# nightlight.net
KiCad netlist of a schematic drawn in EAGLE
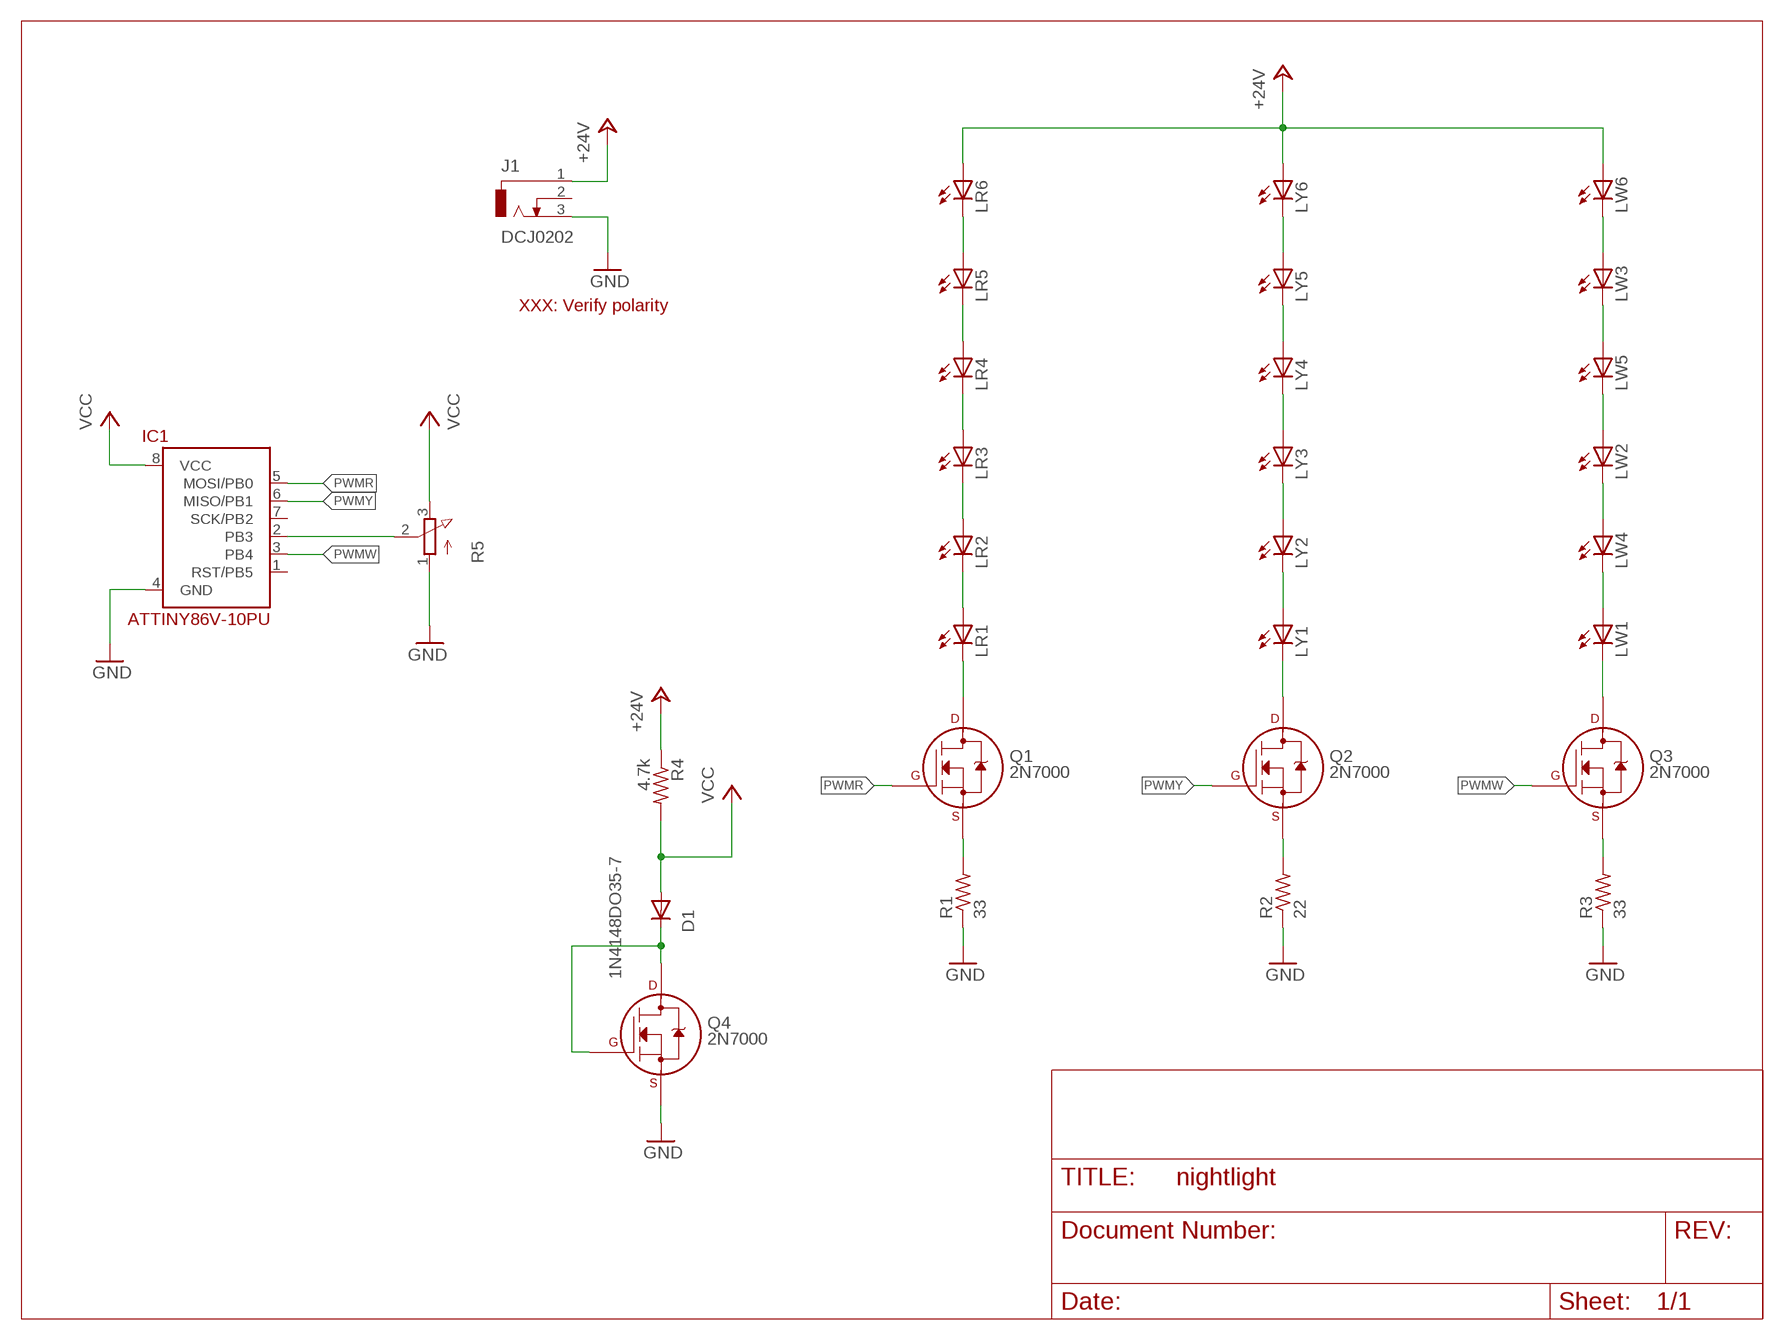
[diagram p0: schematic, sheet 1]

(export (version "E")
  (design (tool "Eeschema 10.0.6"))
  (components
    (comp (ref "D1")
      (value "1N4148DO35-7")
      (footprint "eagle-import:DO35-7")
      (libsource (lib "eagle-import") (part "1N4148DO35-7"))
    )
    (comp (ref "IC1")
      (value "ATTINY86V-10PU")
      (footprint "eagle-import:DIL08")
      (libsource (lib "eagle-import") (part "ATTINY13V-10PU"))
    )
    (comp (ref "J1")
      (value "DCJ0202")
      (footprint "eagle-import:DCJ0202")
      (libsource (lib "eagle-import") (part "DCJ0202"))
    )
    (comp (ref "LR1")
      (value "LED5MM")
      (footprint "eagle-import:LED5MM")
      (libsource (lib "eagle-import") (part "led_LED5MM"))
    )
    (comp (ref "LR2")
      (value "LED5MM")
      (footprint "eagle-import:LED5MM")
      (libsource (lib "eagle-import") (part "led_LED5MM"))
    )
    (comp (ref "LR3")
      (value "LED5MM")
      (footprint "eagle-import:LED5MM")
      (libsource (lib "eagle-import") (part "led_LED5MM"))
    )
    (comp (ref "LR4")
      (value "LED5MM")
      (footprint "eagle-import:LED5MM")
      (libsource (lib "eagle-import") (part "led_LED5MM"))
    )
    (comp (ref "LR5")
      (value "LED5MM")
      (footprint "eagle-import:LED5MM")
      (libsource (lib "eagle-import") (part "led_LED5MM"))
    )
    (comp (ref "LR6")
      (value "LED5MM")
      (footprint "eagle-import:LED5MM")
      (libsource (lib "eagle-import") (part "led_LED5MM"))
    )
    (comp (ref "LW1")
      (value "LED5MM")
      (footprint "eagle-import:LED5MM")
      (libsource (lib "eagle-import") (part "led_LED5MM"))
    )
    (comp (ref "LW2")
      (value "LED5MM")
      (footprint "eagle-import:LED5MM")
      (libsource (lib "eagle-import") (part "led_LED5MM"))
    )
    (comp (ref "LW3")
      (value "LED5MM")
      (footprint "eagle-import:LED5MM")
      (libsource (lib "eagle-import") (part "led_LED5MM"))
    )
    (comp (ref "LW4")
      (value "LED3MM")
      (footprint "eagle-import:LED3MM")
      (libsource (lib "eagle-import") (part "LED3MM"))
    )
    (comp (ref "LW5")
      (value "LED3MM")
      (footprint "eagle-import:LED3MM")
      (libsource (lib "eagle-import") (part "LED3MM"))
    )
    (comp (ref "LW6")
      (value "LED3MM")
      (footprint "eagle-import:LED3MM")
      (libsource (lib "eagle-import") (part "LED3MM"))
    )
    (comp (ref "LY1")
      (value "LED5MM")
      (footprint "eagle-import:LED5MM")
      (libsource (lib "eagle-import") (part "led_LED5MM"))
    )
    (comp (ref "LY2")
      (value "LED5MM")
      (footprint "eagle-import:LED5MM")
      (libsource (lib "eagle-import") (part "led_LED5MM"))
    )
    (comp (ref "LY3")
      (value "LED5MM")
      (footprint "eagle-import:LED5MM")
      (libsource (lib "eagle-import") (part "led_LED5MM"))
    )
    (comp (ref "LY4")
      (value "LED5MM")
      (footprint "eagle-import:LED5MM")
      (libsource (lib "eagle-import") (part "led_LED5MM"))
    )
    (comp (ref "LY5")
      (value "LED5MM")
      (footprint "eagle-import:LED5MM")
      (libsource (lib "eagle-import") (part "led_LED5MM"))
    )
    (comp (ref "LY6")
      (value "LED5MM")
      (footprint "eagle-import:LED5MM")
      (libsource (lib "eagle-import") (part "led_LED5MM"))
    )
    (comp (ref "Q1")
      (value "2N7000")
      (footprint "eagle-import:TO-92")
      (libsource (lib "eagle-import") (part "2N700_TO920"))
    )
    (comp (ref "Q2")
      (value "2N7000")
      (footprint "eagle-import:TO-92")
      (libsource (lib "eagle-import") (part "2N700_TO920"))
    )
    (comp (ref "Q3")
      (value "2N7000")
      (footprint "eagle-import:TO-92")
      (libsource (lib "eagle-import") (part "2N700_TO920"))
    )
    (comp (ref "Q4")
      (value "2N7000")
      (footprint "eagle-import:TO-92")
      (libsource (lib "eagle-import") (part "2N700_TO920"))
    )
    (comp (ref "R1")
      (value "33")
      (footprint "eagle-import:0207_10")
      (libsource (lib "eagle-import") (part "R-US_0207/10"))
    )
    (comp (ref "R2")
      (value "22")
      (footprint "eagle-import:0207_10")
      (libsource (lib "eagle-import") (part "R-US_0207/10"))
    )
    (comp (ref "R3")
      (value "33")
      (footprint "eagle-import:0207_10")
      (libsource (lib "eagle-import") (part "R-US_0207/10"))
    )
    (comp (ref "R4")
      (value "4.7k")
      (footprint "eagle-import:0207_10")
      (libsource (lib "eagle-import") (part "R-US_0207/10"))
    )
    (comp (ref "R5")
      (value "3RP/1610N")
      (footprint "eagle-import:3RP_1610N")
      (libsource (lib "eagle-import") (part "3RP/1610N"))
    )
  )
  (nets
    (net (code "1") (name "+24V") (class "Default")
      (node (ref "J1") (pin "1") (pinfunction "1_1") (pintype "passive"))
      (node (ref "LR6") (pin "A") (pinfunction "A_A") (pintype "passive"))
      (node (ref "LW6") (pin "A") (pinfunction "A_A") (pintype "passive"))
      (node (ref "LY6") (pin "A") (pinfunction "A_A") (pintype "passive"))
      (node (ref "R4") (pin "1") (pinfunction "1_1") (pintype "passive"))
    )
    (net (code "2") (name "GND") (class "Default")
      (node (ref "IC1") (pin "4") (pinfunction "GND_4") (pintype "power_in"))
      (node (ref "J1") (pin "3") (pinfunction "3_3") (pintype "passive"))
      (node (ref "Q4") (pin "1") (pinfunction "S_1") (pintype "bidirectional"))
      (node (ref "R1") (pin "1") (pinfunction "1_1") (pintype "passive"))
      (node (ref "R2") (pin "1") (pinfunction "1_1") (pintype "passive"))
      (node (ref "R3") (pin "1") (pinfunction "1_1") (pintype "passive"))
      (node (ref "R5") (pin "1") (pinfunction "A_1") (pintype "passive"))
    )
    (net (code "3") (name "Net-(IC1-PB3)") (class "Default")
      (node (ref "IC1") (pin "2") (pinfunction "PB3_2") (pintype "bidirectional"))
      (node (ref "R5") (pin "2") (pinfunction "S_2") (pintype "passive"))
    )
    (net (code "4") (name "Net-(LR1-C)") (class "Default")
      (node (ref "LR1") (pin "K") (pinfunction "C_K") (pintype "passive"))
      (node (ref "Q1") (pin "3") (pinfunction "D_3") (pintype "bidirectional"))
    )
    (net (code "5") (name "Net-(LR2-C)") (class "Default")
      (node (ref "LR1") (pin "A") (pinfunction "A_A") (pintype "passive"))
      (node (ref "LR2") (pin "K") (pinfunction "C_K") (pintype "passive"))
    )
    (net (code "6") (name "Net-(LR3-C)") (class "Default")
      (node (ref "LR2") (pin "A") (pinfunction "A_A") (pintype "passive"))
      (node (ref "LR3") (pin "K") (pinfunction "C_K") (pintype "passive"))
    )
    (net (code "7") (name "Net-(LR4-C)") (class "Default")
      (node (ref "LR3") (pin "A") (pinfunction "A_A") (pintype "passive"))
      (node (ref "LR4") (pin "K") (pinfunction "C_K") (pintype "passive"))
    )
    (net (code "8") (name "Net-(LR5-C)") (class "Default")
      (node (ref "LR4") (pin "A") (pinfunction "A_A") (pintype "passive"))
      (node (ref "LR5") (pin "K") (pinfunction "C_K") (pintype "passive"))
    )
    (net (code "9") (name "Net-(LR6-C)") (class "Default")
      (node (ref "LR5") (pin "A") (pinfunction "A_A") (pintype "passive"))
      (node (ref "LR6") (pin "K") (pinfunction "C_K") (pintype "passive"))
    )
    (net (code "10") (name "Net-(LW1-C)") (class "Default")
      (node (ref "LW1") (pin "K") (pinfunction "C_K") (pintype "passive"))
      (node (ref "Q3") (pin "3") (pinfunction "D_3") (pintype "bidirectional"))
    )
    (net (code "11") (name "Net-(LW2-C)") (class "Default")
      (node (ref "LW2") (pin "K") (pinfunction "C_K") (pintype "passive"))
      (node (ref "LW4") (pin "A") (pinfunction "A_A") (pintype "passive"))
    )
    (net (code "12") (name "Net-(LW3-C)") (class "Default")
      (node (ref "LW3") (pin "K") (pinfunction "C_K") (pintype "passive"))
      (node (ref "LW5") (pin "A") (pinfunction "A_A") (pintype "passive"))
    )
    (net (code "13") (name "Net-(LW4-C)") (class "Default")
      (node (ref "LW1") (pin "A") (pinfunction "A_A") (pintype "passive"))
      (node (ref "LW4") (pin "K") (pinfunction "C_K") (pintype "passive"))
    )
    (net (code "14") (name "Net-(LW5-C)") (class "Default")
      (node (ref "LW2") (pin "A") (pinfunction "A_A") (pintype "passive"))
      (node (ref "LW5") (pin "K") (pinfunction "C_K") (pintype "passive"))
    )
    (net (code "15") (name "Net-(LW6-C)") (class "Default")
      (node (ref "LW3") (pin "A") (pinfunction "A_A") (pintype "passive"))
      (node (ref "LW6") (pin "K") (pinfunction "C_K") (pintype "passive"))
    )
    (net (code "16") (name "Net-(LY1-C)") (class "Default")
      (node (ref "LY1") (pin "K") (pinfunction "C_K") (pintype "passive"))
      (node (ref "Q2") (pin "3") (pinfunction "D_3") (pintype "bidirectional"))
    )
    (net (code "17") (name "Net-(LY2-C)") (class "Default")
      (node (ref "LY1") (pin "A") (pinfunction "A_A") (pintype "passive"))
      (node (ref "LY2") (pin "K") (pinfunction "C_K") (pintype "passive"))
    )
    (net (code "18") (name "Net-(LY3-C)") (class "Default")
      (node (ref "LY2") (pin "A") (pinfunction "A_A") (pintype "passive"))
      (node (ref "LY3") (pin "K") (pinfunction "C_K") (pintype "passive"))
    )
    (net (code "19") (name "Net-(LY4-C)") (class "Default")
      (node (ref "LY3") (pin "A") (pinfunction "A_A") (pintype "passive"))
      (node (ref "LY4") (pin "K") (pinfunction "C_K") (pintype "passive"))
    )
    (net (code "20") (name "Net-(LY5-C)") (class "Default")
      (node (ref "LY4") (pin "A") (pinfunction "A_A") (pintype "passive"))
      (node (ref "LY5") (pin "K") (pinfunction "C_K") (pintype "passive"))
    )
    (net (code "21") (name "Net-(LY6-C)") (class "Default")
      (node (ref "LY5") (pin "A") (pinfunction "A_A") (pintype "passive"))
      (node (ref "LY6") (pin "K") (pinfunction "C_K") (pintype "passive"))
    )
    (net (code "22") (name "Net-(Q1-S)") (class "Default")
      (node (ref "Q1") (pin "1") (pinfunction "S_1") (pintype "bidirectional"))
      (node (ref "R1") (pin "2") (pinfunction "2_2") (pintype "passive"))
    )
    (net (code "23") (name "Net-(Q2-S)") (class "Default")
      (node (ref "Q2") (pin "1") (pinfunction "S_1") (pintype "bidirectional"))
      (node (ref "R2") (pin "2") (pinfunction "2_2") (pintype "passive"))
    )
    (net (code "24") (name "Net-(Q3-S)") (class "Default")
      (node (ref "Q3") (pin "1") (pinfunction "S_1") (pintype "bidirectional"))
      (node (ref "R3") (pin "2") (pinfunction "2_2") (pintype "passive"))
    )
    (net (code "25") (name "Net-(Q4-D)") (class "Default")
      (node (ref "D1") (pin "C") (pinfunction "C_C") (pintype "passive"))
      (node (ref "Q4") (pin "2") (pinfunction "G_2") (pintype "tri_state"))
      (node (ref "Q4") (pin "3") (pinfunction "D_3") (pintype "bidirectional"))
    )
    (net (code "26") (name "PWMR") (class "Default")
      (node (ref "IC1") (pin "5") (pinfunction "MOSI/PB0_5") (pintype "bidirectional"))
      (node (ref "Q1") (pin "2") (pinfunction "G_2") (pintype "tri_state"))
    )
    (net (code "27") (name "PWMW") (class "Default")
      (node (ref "IC1") (pin "3") (pinfunction "PB4_3") (pintype "bidirectional"))
      (node (ref "Q3") (pin "2") (pinfunction "G_2") (pintype "tri_state"))
    )
    (net (code "28") (name "PWMY") (class "Default")
      (node (ref "IC1") (pin "6") (pinfunction "MISO/PB1_6") (pintype "bidirectional"))
      (node (ref "Q2") (pin "2") (pinfunction "G_2") (pintype "tri_state"))
    )
    (net (code "29") (name "VCC") (class "Default")
      (node (ref "D1") (pin "A") (pinfunction "A_A") (pintype "passive"))
      (node (ref "IC1") (pin "8") (pinfunction "VCC_8") (pintype "power_in"))
      (node (ref "R4") (pin "2") (pinfunction "2_2") (pintype "passive"))
      (node (ref "R5") (pin "3") (pinfunction "E_3") (pintype "passive"))
    )
    (net (code "30") (name "unconnected-(IC1-RST{slash}PB5-Pad1)") (class "Default")
      (node (ref "IC1") (pin "1") (pinfunction "RST/PB5_1") (pintype "bidirectional"))
    )
    (net (code "31") (name "unconnected-(IC1-SCK{slash}PB2-Pad7)") (class "Default")
      (node (ref "IC1") (pin "7") (pinfunction "SCK/PB2_7") (pintype "bidirectional"))
    )
    (net (code "32") (name "unconnected-(J1-Pad2)") (class "Default")
      (node (ref "J1") (pin "2") (pinfunction "2_2") (pintype "passive"))
    )
  )
)
